# handle.net
KiCad netlist of a schematic drawn in EAGLE
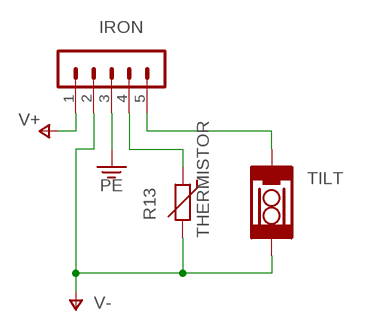
[diagram p0: schematic, sheet 1]

(export (version "E")
  (design (tool "Eeschema 10.0.6"))
  (components
    (comp (ref "IRON")
      (value "MA05-1")
      (footprint "eagle-import:MA05-1")
      (libsource (lib "eagle-import") (part "MA05-1"))
    )
    (comp (ref "R13")
      (value "THERMISTOR")
      (footprint "eagle-import:R-5")
      (libsource (lib "eagle-import") (part "THERMISTOR_R-5"))
    )
    (comp (ref "TILT")
      (value "SQ-SEN-200")
      (footprint "eagle-import:SQ-SEN-200")
      (libsource (lib "eagle-import") (part "SQ-SEN-200"))
    )
  )
  (nets
    (net (code "1") (name "Net-(IRON-Pad4)") (class "Default")
      (node (ref "IRON") (pin "4") (pinfunction "4_4") (pintype "passive"))
      (node (ref "R13") (pin "1") (pinfunction "1_1") (pintype "passive"))
    )
    (net (code "2") (name "Net-(IRON-Pad5)") (class "Default")
      (node (ref "IRON") (pin "5") (pinfunction "5_5") (pintype "passive"))
      (node (ref "TILT") (pin "1") (pinfunction "1_1") (pintype "passive"))
    )
    (net (code "3") (name "PE") (class "Default")
      (node (ref "IRON") (pin "3") (pinfunction "3_3") (pintype "passive"))
    )
    (net (code "4") (name "V+") (class "Default")
      (node (ref "IRON") (pin "1") (pinfunction "1_1") (pintype "passive"))
    )
    (net (code "5") (name "V-") (class "Default")
      (node (ref "IRON") (pin "2") (pinfunction "2_2") (pintype "passive"))
      (node (ref "R13") (pin "2") (pinfunction "2_2") (pintype "passive"))
      (node (ref "TILT") (pin "2") (pinfunction "2_2") (pintype "passive"))
    )
  )
)
